# Front_panel_FFC.net
KiCad netlist of a schematic drawn in Altium Designer
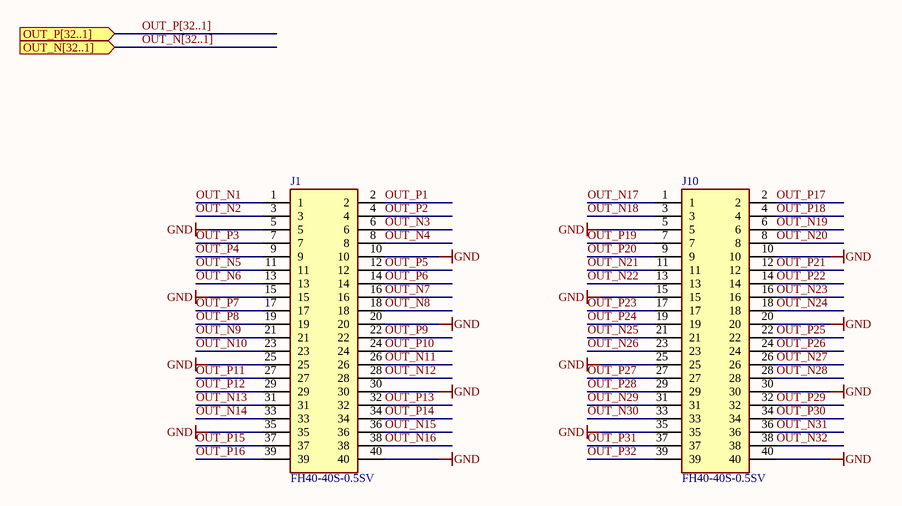
[diagram p0: Front_panel_FFC.SchDoc]

(export (version "E")
  (design (tool "Eeschema 10.0.6"))
  (components
    (comp (ref "J1")
      (value "FH40-40S-0.5SV")
      (footprint "FH4040S05SV")
      (description "Connector")
      (fields (field (name "MOUSER PART NUMBER") "798-FH40-40S-0.5SV"))
      (libsource (lib "Integrated_Library_LOADER") (part "FH40-40S-0.5SV"))
    )
    (comp (ref "J10")
      (value "FH40-40S-0.5SV")
      (footprint "FH4040S05SV")
      (description "Connector")
      (fields (field (name "MOUSER PART NUMBER") "798-FH40-40S-0.5SV"))
      (libsource (lib "Integrated_Library_LOADER") (part "FH40-40S-0.5SV"))
    )
  )
  (nets
    (net (code "1") (name "/OUT_N1") (class "Default")
      (node (ref "J1") (pin "1") (pinfunction "1_1") (pintype "passive"))
    )
    (net (code "2") (name "/OUT_N2") (class "Default")
      (node (ref "J1") (pin "3") (pinfunction "3_3") (pintype "passive"))
    )
    (net (code "3") (name "/OUT_N3") (class "Default")
      (node (ref "J1") (pin "6") (pinfunction "6_6") (pintype "passive"))
    )
    (net (code "4") (name "/OUT_N4") (class "Default")
      (node (ref "J1") (pin "8") (pinfunction "8_8") (pintype "passive"))
    )
    (net (code "5") (name "/OUT_N5") (class "Default")
      (node (ref "J1") (pin "11") (pinfunction "11_11") (pintype "passive"))
    )
    (net (code "6") (name "/OUT_N6") (class "Default")
      (node (ref "J1") (pin "13") (pinfunction "13_13") (pintype "passive"))
    )
    (net (code "7") (name "/OUT_N7") (class "Default")
      (node (ref "J1") (pin "16") (pinfunction "16_16") (pintype "passive"))
    )
    (net (code "8") (name "/OUT_N8") (class "Default")
      (node (ref "J1") (pin "18") (pinfunction "18_18") (pintype "passive"))
    )
    (net (code "9") (name "/OUT_N9") (class "Default")
      (node (ref "J1") (pin "21") (pinfunction "21_21") (pintype "passive"))
    )
    (net (code "10") (name "/OUT_N10") (class "Default")
      (node (ref "J1") (pin "23") (pinfunction "23_23") (pintype "passive"))
    )
    (net (code "11") (name "/OUT_N11") (class "Default")
      (node (ref "J1") (pin "26") (pinfunction "26_26") (pintype "passive"))
    )
    (net (code "12") (name "/OUT_N12") (class "Default")
      (node (ref "J1") (pin "28") (pinfunction "28_28") (pintype "passive"))
    )
    (net (code "13") (name "/OUT_N13") (class "Default")
      (node (ref "J1") (pin "31") (pinfunction "31_31") (pintype "passive"))
    )
    (net (code "14") (name "/OUT_N14") (class "Default")
      (node (ref "J1") (pin "33") (pinfunction "33_33") (pintype "passive"))
    )
    (net (code "15") (name "/OUT_N15") (class "Default")
      (node (ref "J1") (pin "36") (pinfunction "36_36") (pintype "passive"))
    )
    (net (code "16") (name "/OUT_N16") (class "Default")
      (node (ref "J1") (pin "38") (pinfunction "38_38") (pintype "passive"))
    )
    (net (code "17") (name "/OUT_N17") (class "Default")
      (node (ref "J10") (pin "1") (pinfunction "1_1") (pintype "passive"))
    )
    (net (code "18") (name "/OUT_N18") (class "Default")
      (node (ref "J10") (pin "3") (pinfunction "3_3") (pintype "passive"))
    )
    (net (code "19") (name "/OUT_N19") (class "Default")
      (node (ref "J10") (pin "6") (pinfunction "6_6") (pintype "passive"))
    )
    (net (code "20") (name "/OUT_N20") (class "Default")
      (node (ref "J10") (pin "8") (pinfunction "8_8") (pintype "passive"))
    )
    (net (code "21") (name "/OUT_N21") (class "Default")
      (node (ref "J10") (pin "11") (pinfunction "11_11") (pintype "passive"))
    )
    (net (code "22") (name "/OUT_N22") (class "Default")
      (node (ref "J10") (pin "13") (pinfunction "13_13") (pintype "passive"))
    )
    (net (code "23") (name "/OUT_N23") (class "Default")
      (node (ref "J10") (pin "16") (pinfunction "16_16") (pintype "passive"))
    )
    (net (code "24") (name "/OUT_N24") (class "Default")
      (node (ref "J10") (pin "18") (pinfunction "18_18") (pintype "passive"))
    )
    (net (code "25") (name "/OUT_N25") (class "Default")
      (node (ref "J10") (pin "21") (pinfunction "21_21") (pintype "passive"))
    )
    (net (code "26") (name "/OUT_N26") (class "Default")
      (node (ref "J10") (pin "23") (pinfunction "23_23") (pintype "passive"))
    )
    (net (code "27") (name "/OUT_N27") (class "Default")
      (node (ref "J10") (pin "26") (pinfunction "26_26") (pintype "passive"))
    )
    (net (code "28") (name "/OUT_N28") (class "Default")
      (node (ref "J10") (pin "28") (pinfunction "28_28") (pintype "passive"))
    )
    (net (code "29") (name "/OUT_N29") (class "Default")
      (node (ref "J10") (pin "31") (pinfunction "31_31") (pintype "passive"))
    )
    (net (code "30") (name "/OUT_N30") (class "Default")
      (node (ref "J10") (pin "33") (pinfunction "33_33") (pintype "passive"))
    )
    (net (code "31") (name "/OUT_N31") (class "Default")
      (node (ref "J10") (pin "36") (pinfunction "36_36") (pintype "passive"))
    )
    (net (code "32") (name "/OUT_N32") (class "Default")
      (node (ref "J10") (pin "38") (pinfunction "38_38") (pintype "passive"))
    )
    (net (code "34") (name "/OUT_P1") (class "Default")
      (node (ref "J1") (pin "2") (pinfunction "2_2") (pintype "passive"))
    )
    (net (code "35") (name "/OUT_P2") (class "Default")
      (node (ref "J1") (pin "4") (pinfunction "4_4") (pintype "passive"))
    )
    (net (code "36") (name "/OUT_P3") (class "Default")
      (node (ref "J1") (pin "7") (pinfunction "7_7") (pintype "passive"))
    )
    (net (code "37") (name "/OUT_P4") (class "Default")
      (node (ref "J1") (pin "9") (pinfunction "9_9") (pintype "passive"))
    )
    (net (code "38") (name "/OUT_P5") (class "Default")
      (node (ref "J1") (pin "12") (pinfunction "12_12") (pintype "passive"))
    )
    (net (code "39") (name "/OUT_P6") (class "Default")
      (node (ref "J1") (pin "14") (pinfunction "14_14") (pintype "passive"))
    )
    (net (code "40") (name "/OUT_P7") (class "Default")
      (node (ref "J1") (pin "17") (pinfunction "17_17") (pintype "passive"))
    )
    (net (code "41") (name "/OUT_P8") (class "Default")
      (node (ref "J1") (pin "19") (pinfunction "19_19") (pintype "passive"))
    )
    (net (code "42") (name "/OUT_P9") (class "Default")
      (node (ref "J1") (pin "22") (pinfunction "22_22") (pintype "passive"))
    )
    (net (code "43") (name "/OUT_P10") (class "Default")
      (node (ref "J1") (pin "24") (pinfunction "24_24") (pintype "passive"))
    )
    (net (code "44") (name "/OUT_P11") (class "Default")
      (node (ref "J1") (pin "27") (pinfunction "27_27") (pintype "passive"))
    )
    (net (code "45") (name "/OUT_P12") (class "Default")
      (node (ref "J1") (pin "29") (pinfunction "29_29") (pintype "passive"))
    )
    (net (code "46") (name "/OUT_P13") (class "Default")
      (node (ref "J1") (pin "32") (pinfunction "32_32") (pintype "passive"))
    )
    (net (code "47") (name "/OUT_P14") (class "Default")
      (node (ref "J1") (pin "34") (pinfunction "34_34") (pintype "passive"))
    )
    (net (code "48") (name "/OUT_P15") (class "Default")
      (node (ref "J1") (pin "37") (pinfunction "37_37") (pintype "passive"))
    )
    (net (code "49") (name "/OUT_P16") (class "Default")
      (node (ref "J1") (pin "39") (pinfunction "39_39") (pintype "passive"))
    )
    (net (code "50") (name "/OUT_P17") (class "Default")
      (node (ref "J10") (pin "2") (pinfunction "2_2") (pintype "passive"))
    )
    (net (code "51") (name "/OUT_P18") (class "Default")
      (node (ref "J10") (pin "4") (pinfunction "4_4") (pintype "passive"))
    )
    (net (code "52") (name "/OUT_P19") (class "Default")
      (node (ref "J10") (pin "7") (pinfunction "7_7") (pintype "passive"))
    )
    (net (code "53") (name "/OUT_P20") (class "Default")
      (node (ref "J10") (pin "9") (pinfunction "9_9") (pintype "passive"))
    )
    (net (code "54") (name "/OUT_P21") (class "Default")
      (node (ref "J10") (pin "12") (pinfunction "12_12") (pintype "passive"))
    )
    (net (code "55") (name "/OUT_P22") (class "Default")
      (node (ref "J10") (pin "14") (pinfunction "14_14") (pintype "passive"))
    )
    (net (code "56") (name "/OUT_P23") (class "Default")
      (node (ref "J10") (pin "17") (pinfunction "17_17") (pintype "passive"))
    )
    (net (code "57") (name "/OUT_P24") (class "Default")
      (node (ref "J10") (pin "19") (pinfunction "19_19") (pintype "passive"))
    )
    (net (code "58") (name "/OUT_P25") (class "Default")
      (node (ref "J10") (pin "22") (pinfunction "22_22") (pintype "passive"))
    )
    (net (code "59") (name "/OUT_P26") (class "Default")
      (node (ref "J10") (pin "24") (pinfunction "24_24") (pintype "passive"))
    )
    (net (code "60") (name "/OUT_P27") (class "Default")
      (node (ref "J10") (pin "27") (pinfunction "27_27") (pintype "passive"))
    )
    (net (code "61") (name "/OUT_P28") (class "Default")
      (node (ref "J10") (pin "29") (pinfunction "29_29") (pintype "passive"))
    )
    (net (code "62") (name "/OUT_P29") (class "Default")
      (node (ref "J10") (pin "32") (pinfunction "32_32") (pintype "passive"))
    )
    (net (code "63") (name "/OUT_P30") (class "Default")
      (node (ref "J10") (pin "34") (pinfunction "34_34") (pintype "passive"))
    )
    (net (code "64") (name "/OUT_P31") (class "Default")
      (node (ref "J10") (pin "37") (pinfunction "37_37") (pintype "passive"))
    )
    (net (code "65") (name "/OUT_P32") (class "Default")
      (node (ref "J10") (pin "39") (pinfunction "39_39") (pintype "passive"))
    )
    (net (code "67") (name "GND") (class "Default")
      (node (ref "J1") (pin "10") (pinfunction "10_10") (pintype "passive"))
      (node (ref "J1") (pin "15") (pinfunction "15_15") (pintype "passive"))
      (node (ref "J1") (pin "20") (pinfunction "20_20") (pintype "passive"))
      (node (ref "J1") (pin "25") (pinfunction "25_25") (pintype "passive"))
      (node (ref "J1") (pin "30") (pinfunction "30_30") (pintype "passive"))
      (node (ref "J1") (pin "35") (pinfunction "35_35") (pintype "passive"))
      (node (ref "J1") (pin "40") (pinfunction "40_40") (pintype "passive"))
      (node (ref "J1") (pin "5") (pinfunction "5_5") (pintype "passive"))
      (node (ref "J10") (pin "10") (pinfunction "10_10") (pintype "passive"))
      (node (ref "J10") (pin "15") (pinfunction "15_15") (pintype "passive"))
      (node (ref "J10") (pin "20") (pinfunction "20_20") (pintype "passive"))
      (node (ref "J10") (pin "25") (pinfunction "25_25") (pintype "passive"))
      (node (ref "J10") (pin "30") (pinfunction "30_30") (pintype "passive"))
      (node (ref "J10") (pin "35") (pinfunction "35_35") (pintype "passive"))
      (node (ref "J10") (pin "40") (pinfunction "40_40") (pintype "passive"))
      (node (ref "J10") (pin "5") (pinfunction "5_5") (pintype "passive"))
    )
  )
)
